# transc_MRF24J40MA.net
KiCad netlist of a schematic drawn in Altium Designer
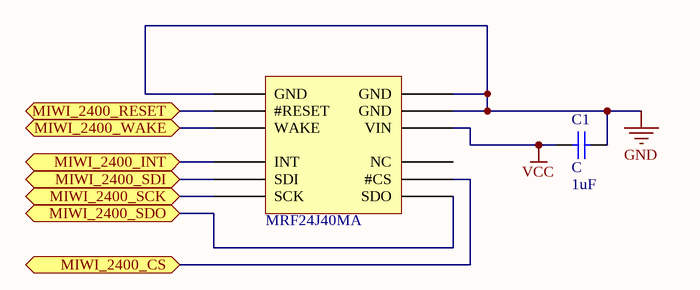
[diagram p0: transc_MRF24J40MA.SchDoc]

(export (version "E")
  (design (tool "Eeschema 10.0.6"))
  (components
    (comp (ref "C1")
      (value "C")
      (footprint "RAD-0.3")
      (description "Capacitor")
      (fields (field (name "ALTIUM_VALUE") "1uF") (field (name "PUBLISHER") "Altium Limited"))
      (libsource (lib "Miscellaneous Devices") (part "Cap"))
    )
    (comp (ref "MRF24J40MA")
      (value "MRF24J40MA")
      (footprint "MRF24J40MA")
      (description "Microchip RF radio")
      (libsource (lib "LSI") (part "MRF24J40MA"))
    )
  )
  (nets
    (net (code "1") (name "/MIWI_2400_CS") (class "Default")
      (node (ref "MRF24J40MA") (pin "11") (pinfunction "#CS_11") (pintype "passive"))
    )
    (net (code "2") (name "/MIWI_2400_INT") (class "Default")
      (node (ref "MRF24J40MA") (pin "4") (pinfunction "INT_4") (pintype "passive"))
    )
    (net (code "3") (name "/MIWI_2400_RESET") (class "Default")
      (node (ref "MRF24J40MA") (pin "2") (pinfunction "#RESET_2") (pintype "passive"))
    )
    (net (code "4") (name "/MIWI_2400_SCK") (class "Default")
      (node (ref "MRF24J40MA") (pin "6") (pinfunction "SCK_6") (pintype "passive"))
    )
    (net (code "5") (name "/MIWI_2400_SDI") (class "Default")
      (node (ref "MRF24J40MA") (pin "5") (pinfunction "SDI_5") (pintype "passive"))
    )
    (net (code "6") (name "/MIWI_2400_SDO") (class "Default")
      (node (ref "MRF24J40MA") (pin "12") (pinfunction "SDO_12") (pintype "passive"))
    )
    (net (code "7") (name "/MIWI_2400_WAKE") (class "Default")
      (node (ref "MRF24J40MA") (pin "3") (pinfunction "WAKE_3") (pintype "passive"))
    )
    (net (code "8") (name "GND") (class "Default")
      (node (ref "C1") (pin "2") (pinfunction "2_2") (pintype "passive"))
      (node (ref "MRF24J40MA") (pin "1") (pinfunction "GND_1") (pintype "passive"))
      (node (ref "MRF24J40MA") (pin "7") (pinfunction "GND_7") (pintype "passive"))
      (node (ref "MRF24J40MA") (pin "8") (pinfunction "GND_8") (pintype "passive"))
    )
    (net (code "9") (name "VCC") (class "Default")
      (node (ref "C1") (pin "1") (pinfunction "1_1") (pintype "passive"))
      (node (ref "MRF24J40MA") (pin "9") (pinfunction "VIN_9") (pintype "passive"))
    )
    (net (code "10") (name "unconnected-(MRF24J40MA-NC-Pad10)") (class "Default")
      (node (ref "MRF24J40MA") (pin "10") (pinfunction "NC_10") (pintype "passive"))
    )
  )
)
